# SCH.net
KiCad netlist of a schematic drawn in Altium Designer
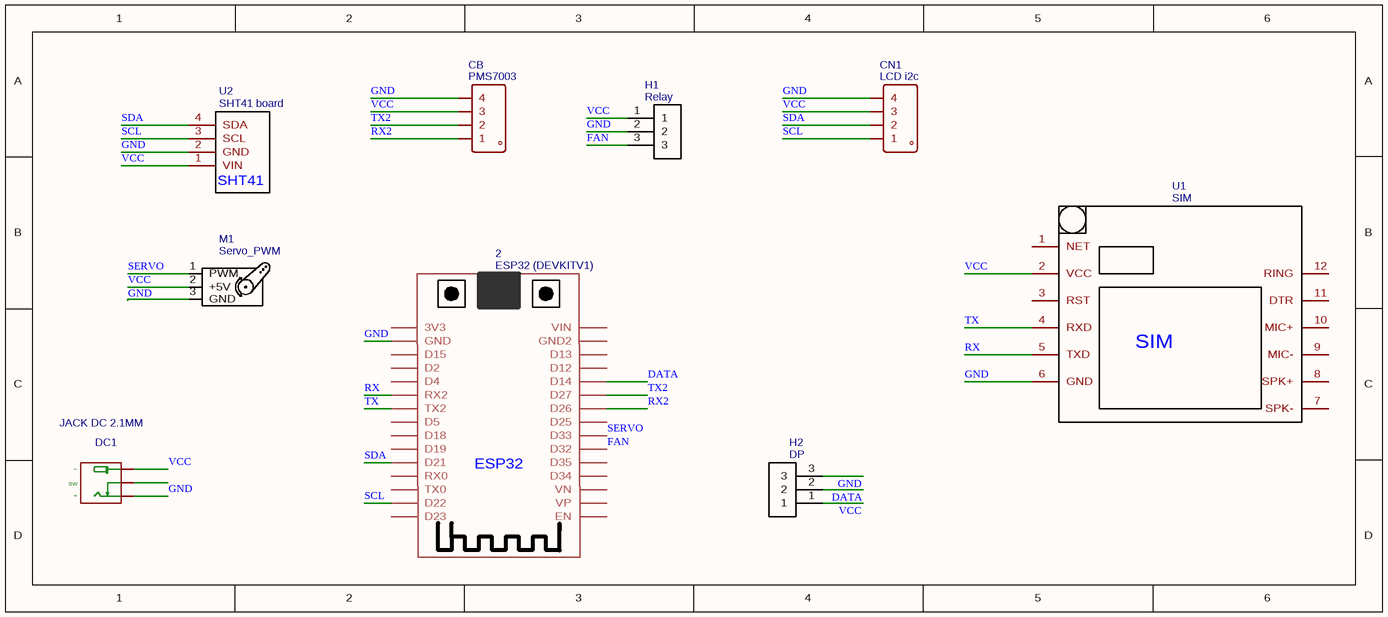
[diagram p0: SCH.schdoc]

(export (version "E")
  (design (tool "Eeschema 10.0.6"))
  (components
    (comp (ref "2")
      (value "ESP32 (DEVKITV1)")
      (fields (field (name "CONTRIBUTOR") "savanpandey31"))
      (libsource (lib "altium-import") (part "root_2_ESP32 (DEVKITV1)_"))
    )
    (comp (ref "CB")
      (value "PMS7003")
      (fields (field (name "CONTRIBUTOR") "mKenfenheuer"))
      (libsource (lib "altium-import") (part "root_2_PMS7003_"))
    )
    (comp (ref "CN1")
      (value "LCD i2c")
      (fields (field (name "CONTRIBUTOR") "mKenfenheuer"))
      (libsource (lib "altium-import") (part "root_2_LCD i2c_"))
    )
    (comp (ref "DC1")
      (value "JACK DC 2.1MM")
      (fields
        (field (name "MANUFACTURER") "SHOU HAN")
        (field (name "MANUFACTURER PART") "DC022")
        (field (name "CONTRIBUTOR") "ricarod")
      )
      (libsource (lib "altium-import") (part "root_0_JACK DC 2.1MM_"))
    )
    (comp (ref "H1")
      (value "Relay")
      (fields (field (name "CONTRIBUTOR") "patriciamoy857"))
      (libsource (lib "altium-import") (part "root_0_Relay_"))
    )
    (comp (ref "H2")
      (value "DP")
      (fields (field (name "CONTRIBUTOR") "patriciamoy857"))
      (libsource (lib "altium-import") (part "root_2_DP_"))
    )
    (comp (ref "M1")
      (value "Servo_PWM")
      (fields (field (name "CONTRIBUTOR") "JSiderius"))
      (libsource (lib "altium-import") (part "root_0_Servo_PWM_"))
    )
    (comp (ref "U1")
      (value "SIM")
      (fields (field (name "MANUFACTURER") "ARCELI") (field (name "CONTRIBUTOR") "ulf.modig"))
      (libsource (lib "altium-import") (part "root_0_SIM_"))
    )
    (comp (ref "U2")
      (value "SHT41 board")
      (fields (field (name "CONTRIBUTOR") "mienkofax"))
      (libsource (lib "altium-import") (part "root_2_SHT41 board_"))
    )
  )
  (nets
    (net (code "1") (name "/DATA") (class "Default")
      (node (ref "2") (pin "D14") (pinfunction "D14_D14") (pintype "passive"))
      (node (ref "H2") (pin "2") (pinfunction "2_2") (pintype "passive"))
    )
    (net (code "2") (name "/FAN") (class "Default")
      (node (ref "2") (pin "D32") (pinfunction "D32_D32") (pintype "passive"))
      (node (ref "H1") (pin "3") (pinfunction "3_3") (pintype "passive"))
    )
    (net (code "3") (name "/GND") (class "Default")
      (node (ref "2") (pin "GND") (pinfunction "GND_GND") (pintype "passive"))
      (node (ref "CB") (pin "4") (pinfunction "4_4") (pintype "passive"))
      (node (ref "CN1") (pin "4") (pinfunction "4_4") (pintype "passive"))
      (node (ref "DC1") (pin "+") (pinfunction "+_+") (pintype "passive"))
      (node (ref "H1") (pin "2") (pinfunction "2_2") (pintype "passive"))
      (node (ref "H2") (pin "3") (pinfunction "3_3") (pintype "passive"))
      (node (ref "M1") (pin "3") (pinfunction "GND_3") (pintype "passive"))
      (node (ref "U1") (pin "6") (pinfunction "GND_6") (pintype "passive"))
      (node (ref "U2") (pin "2") (pinfunction "GND_2") (pintype "passive"))
    )
    (net (code "4") (name "/RX") (class "Default")
      (node (ref "2") (pin "RX2") (pinfunction "RX2_RX2") (pintype "passive"))
      (node (ref "U1") (pin "5") (pinfunction "TXD_5") (pintype "passive"))
    )
    (net (code "5") (name "/RX2") (class "Default")
      (node (ref "2") (pin "D26") (pinfunction "D26_D26") (pintype "passive"))
      (node (ref "CB") (pin "1") (pinfunction "1_1") (pintype "passive"))
    )
    (net (code "6") (name "/SCL") (class "Default")
      (node (ref "2") (pin "D22") (pinfunction "D22_D22") (pintype "passive"))
      (node (ref "CN1") (pin "1") (pinfunction "1_1") (pintype "passive"))
      (node (ref "U2") (pin "3") (pinfunction "SCL_3") (pintype "passive"))
    )
    (net (code "7") (name "/SDA") (class "Default")
      (node (ref "2") (pin "D21") (pinfunction "D21_D21") (pintype "passive"))
      (node (ref "CN1") (pin "2") (pinfunction "2_2") (pintype "passive"))
      (node (ref "U2") (pin "4") (pinfunction "SDA_4") (pintype "passive"))
    )
    (net (code "8") (name "/SERVO") (class "Default")
      (node (ref "2") (pin "D33") (pinfunction "D33_D33") (pintype "passive"))
      (node (ref "M1") (pin "1") (pinfunction "PWM_1") (pintype "passive"))
    )
    (net (code "9") (name "/TX") (class "Default")
      (node (ref "2") (pin "TX2") (pinfunction "TX2_TX2") (pintype "passive"))
      (node (ref "U1") (pin "4") (pinfunction "RXD_4") (pintype "passive"))
    )
    (net (code "10") (name "/TX2") (class "Default")
      (node (ref "2") (pin "D27") (pinfunction "D27_D27") (pintype "passive"))
      (node (ref "CB") (pin "2") (pinfunction "2_2") (pintype "passive"))
    )
    (net (code "11") (name "/VCC") (class "Default")
      (node (ref "CB") (pin "3") (pinfunction "3_3") (pintype "passive"))
      (node (ref "CN1") (pin "3") (pinfunction "3_3") (pintype "passive"))
      (node (ref "DC1") (pin "-") (pinfunction "-_-") (pintype "passive"))
      (node (ref "H1") (pin "1") (pinfunction "1_1") (pintype "passive"))
      (node (ref "H2") (pin "1") (pinfunction "1_1") (pintype "passive"))
      (node (ref "M1") (pin "2") (pinfunction "+5V_2") (pintype "passive"))
      (node (ref "U1") (pin "2") (pinfunction "VCC_2") (pintype "passive"))
      (node (ref "U2") (pin "1") (pinfunction "VIN_1") (pintype "passive"))
    )
    (net (code "12") (name "unconnected-(2-Pad3V3)") (class "Default")
      (node (ref "2") (pin "3V3") (pinfunction "3V3_3V3") (pintype "passive"))
    )
    (net (code "13") (name "unconnected-(2-PadD2)") (class "Default")
      (node (ref "2") (pin "D2") (pinfunction "D2_D2") (pintype "passive"))
    )
    (net (code "14") (name "unconnected-(2-PadD4)") (class "Default")
      (node (ref "2") (pin "D4") (pinfunction "D4_D4") (pintype "passive"))
    )
    (net (code "15") (name "unconnected-(2-PadD5)") (class "Default")
      (node (ref "2") (pin "D5") (pinfunction "D5_D5") (pintype "passive"))
    )
    (net (code "16") (name "unconnected-(2-PadD12)") (class "Default")
      (node (ref "2") (pin "D12") (pinfunction "D12_D12") (pintype "passive"))
    )
    (net (code "17") (name "unconnected-(2-PadD13)") (class "Default")
      (node (ref "2") (pin "D13") (pinfunction "D13_D13") (pintype "passive"))
    )
    (net (code "18") (name "unconnected-(2-PadD15)") (class "Default")
      (node (ref "2") (pin "D15") (pinfunction "D15_D15") (pintype "passive"))
    )
    (net (code "19") (name "unconnected-(2-PadD18)") (class "Default")
      (node (ref "2") (pin "D18") (pinfunction "D18_D18") (pintype "passive"))
    )
    (net (code "20") (name "unconnected-(2-PadD19)") (class "Default")
      (node (ref "2") (pin "D19") (pinfunction "D19_D19") (pintype "passive"))
    )
    (net (code "21") (name "unconnected-(2-PadD23)") (class "Default")
      (node (ref "2") (pin "D23") (pinfunction "D23_D23") (pintype "passive"))
    )
    (net (code "22") (name "unconnected-(2-PadD25)") (class "Default")
      (node (ref "2") (pin "D25") (pinfunction "D25_D25") (pintype "passive"))
    )
    (net (code "23") (name "unconnected-(2-PadD34)") (class "Default")
      (node (ref "2") (pin "D34") (pinfunction "D34_D34") (pintype "passive"))
    )
    (net (code "24") (name "unconnected-(2-PadD35)") (class "Default")
      (node (ref "2") (pin "D35") (pinfunction "D35_D35") (pintype "passive"))
    )
    (net (code "25") (name "unconnected-(2-PadEN)") (class "Default")
      (node (ref "2") (pin "EN") (pinfunction "EN_EN") (pintype "passive"))
    )
    (net (code "26") (name "unconnected-(2-PadGND2)") (class "Default")
      (node (ref "2") (pin "GND2") (pinfunction "GND2_GND2") (pintype "passive"))
    )
    (net (code "27") (name "unconnected-(2-PadRX0)") (class "Default")
      (node (ref "2") (pin "RX0") (pinfunction "RX0_RX0") (pintype "passive"))
    )
    (net (code "28") (name "unconnected-(2-PadTX0)") (class "Default")
      (node (ref "2") (pin "TX0") (pinfunction "TX0_TX0") (pintype "passive"))
    )
    (net (code "29") (name "unconnected-(2-PadVIN)") (class "Default")
      (node (ref "2") (pin "VIN") (pinfunction "VIN_VIN") (pintype "passive"))
    )
    (net (code "30") (name "unconnected-(2-PadVN)") (class "Default")
      (node (ref "2") (pin "VN") (pinfunction "VN_VN") (pintype "passive"))
    )
    (net (code "31") (name "unconnected-(2-PadVP)") (class "Default")
      (node (ref "2") (pin "VP") (pinfunction "VP_VP") (pintype "passive"))
    )
    (net (code "32") (name "unconnected-(DC1-PadSW)") (class "Default")
      (node (ref "DC1") (pin "SW") (pinfunction "SW_SW") (pintype "passive"))
    )
    (net (code "33") (name "unconnected-(U1-DTR-Pad11)") (class "Default")
      (node (ref "U1") (pin "11") (pinfunction "DTR_11") (pintype "passive"))
    )
    (net (code "34") (name "unconnected-(U1-MIC+-Pad10)") (class "Default")
      (node (ref "U1") (pin "10") (pinfunction "MIC+_10") (pintype "passive"))
    )
    (net (code "35") (name "unconnected-(U1-MIC--Pad9)") (class "Default")
      (node (ref "U1") (pin "9") (pinfunction "MIC-_9") (pintype "passive"))
    )
    (net (code "36") (name "unconnected-(U1-NET-Pad1)") (class "Default")
      (node (ref "U1") (pin "1") (pinfunction "NET_1") (pintype "passive"))
    )
    (net (code "37") (name "unconnected-(U1-RING-Pad12)") (class "Default")
      (node (ref "U1") (pin "12") (pinfunction "RING_12") (pintype "passive"))
    )
    (net (code "38") (name "unconnected-(U1-RST-Pad3)") (class "Default")
      (node (ref "U1") (pin "3") (pinfunction "RST_3") (pintype "passive"))
    )
    (net (code "39") (name "unconnected-(U1-SPK+-Pad8)") (class "Default")
      (node (ref "U1") (pin "8") (pinfunction "SPK+_8") (pintype "passive"))
    )
    (net (code "40") (name "unconnected-(U1-SPK--Pad7)") (class "Default")
      (node (ref "U1") (pin "7") (pinfunction "SPK-_7") (pintype "passive"))
    )
  )
)
